# PA.net
KiCad netlist of a schematic drawn in EAGLE
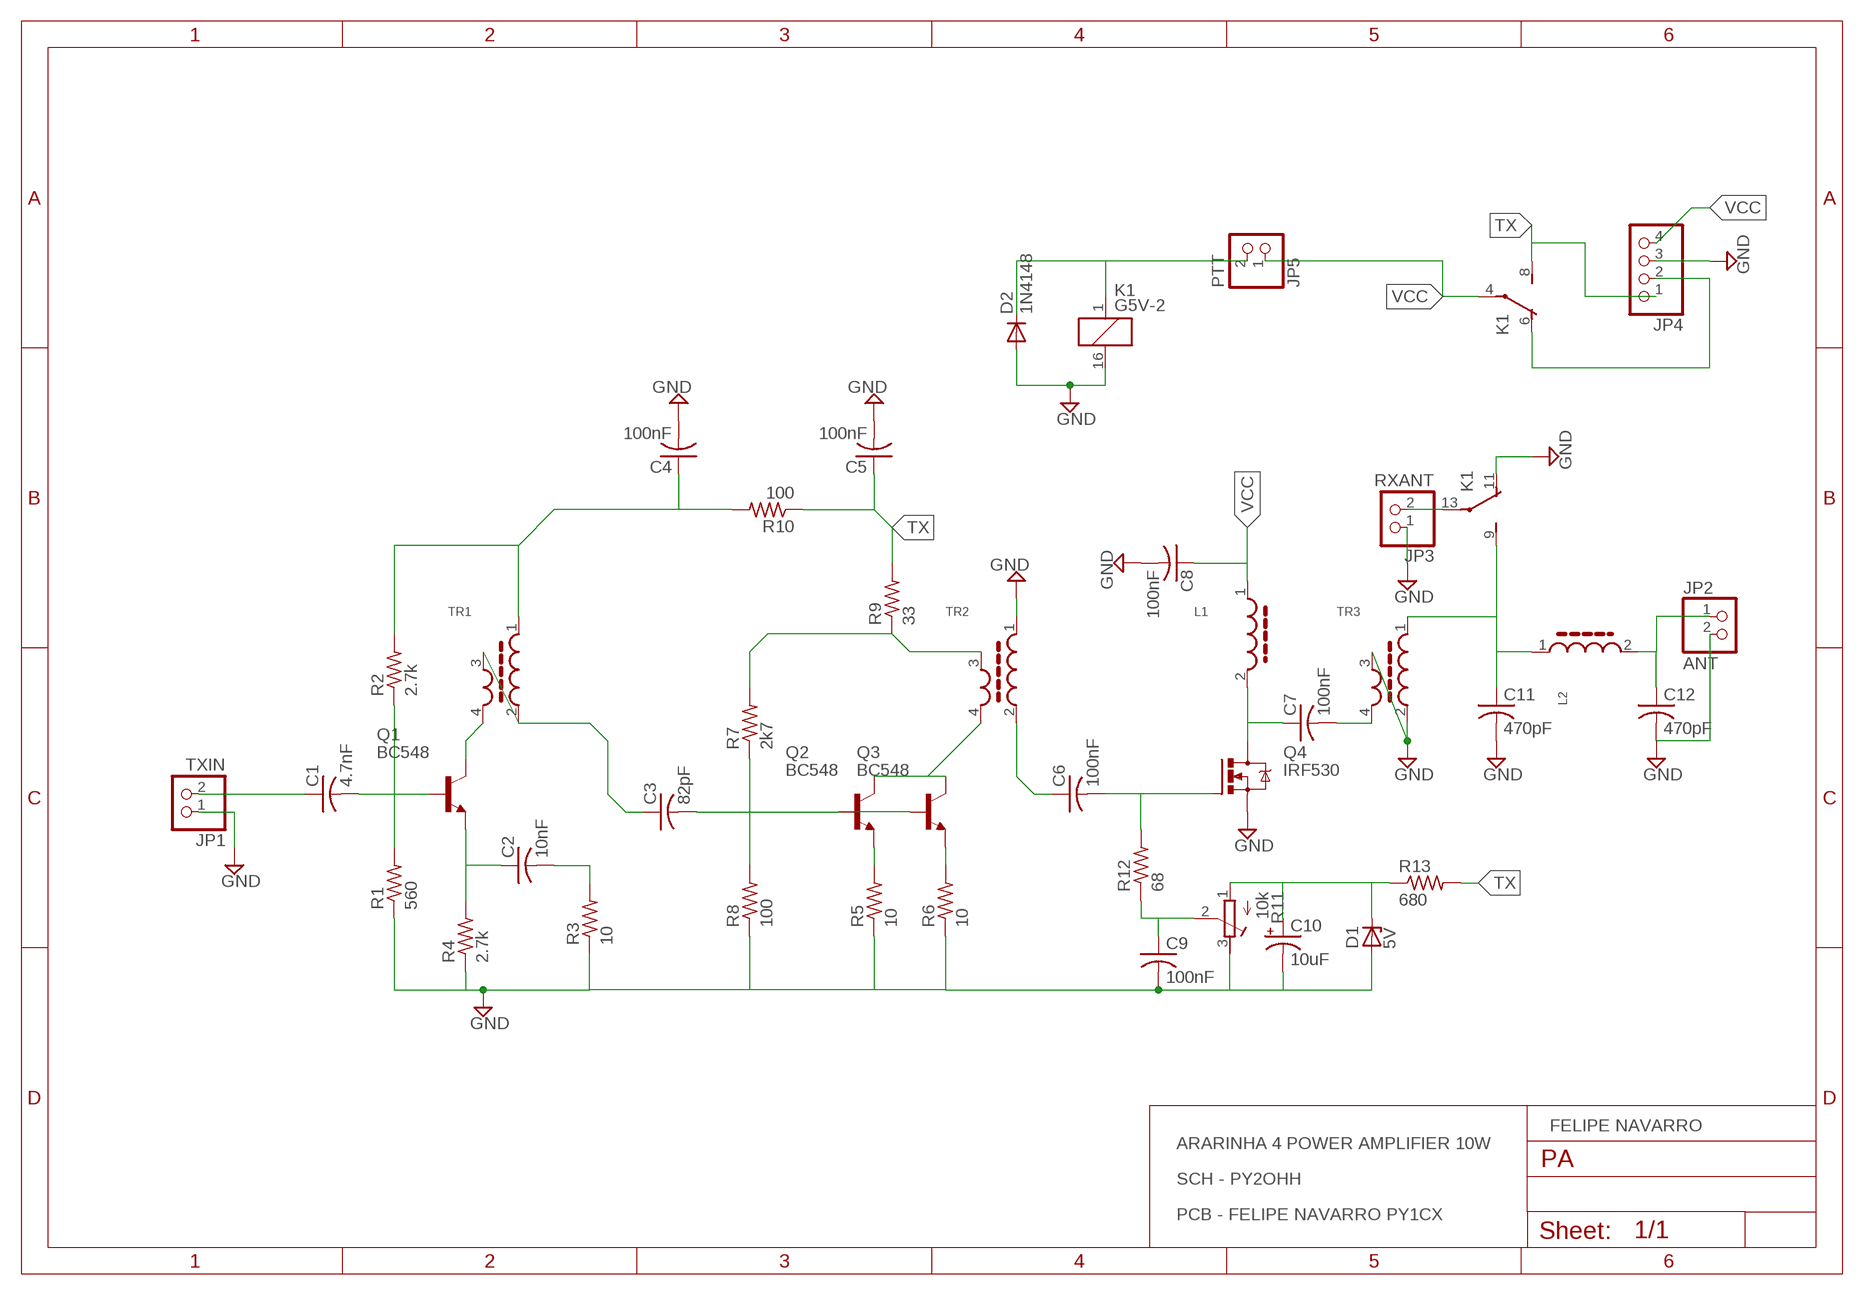
[diagram p0: schematic, sheet 1]

(export (version "E")
  (design (tool "Eeschema 10.0.6"))
  (components
    (comp (ref "C1")
      (value "4.7nF")
      (footprint "eagle-import:C050-030X075")
      (libsource (lib "eagle-import") (part "C-US050-030X075"))
    )
    (comp (ref "C2")
      (value "10nF")
      (footprint "eagle-import:C050-030X075")
      (libsource (lib "eagle-import") (part "C-US050-030X075"))
    )
    (comp (ref "C3")
      (value "82pF")
      (footprint "eagle-import:C050-030X075")
      (libsource (lib "eagle-import") (part "C-US050-030X075"))
    )
    (comp (ref "C4")
      (value "100nF")
      (footprint "eagle-import:C050-030X075")
      (libsource (lib "eagle-import") (part "C-US050-030X075"))
    )
    (comp (ref "C5")
      (value "100nF")
      (footprint "eagle-import:C050-030X075")
      (libsource (lib "eagle-import") (part "C-US050-030X075"))
    )
    (comp (ref "C6")
      (value "100nF")
      (footprint "eagle-import:C050-030X075")
      (libsource (lib "eagle-import") (part "C-US050-030X075"))
    )
    (comp (ref "C7")
      (value "100nF")
      (footprint "eagle-import:C050-030X075")
      (libsource (lib "eagle-import") (part "C-US050-030X075"))
    )
    (comp (ref "C8")
      (value "100nF")
      (footprint "eagle-import:C050-030X075")
      (libsource (lib "eagle-import") (part "C-US050-030X075"))
    )
    (comp (ref "C9")
      (value "100nF")
      (footprint "eagle-import:C050-030X075")
      (libsource (lib "eagle-import") (part "C-US050-030X075"))
    )
    (comp (ref "C10")
      (value "10uF")
      (footprint "eagle-import:E3,5-8")
      (libsource (lib "eagle-import") (part "CPOL-USE3.5-8"))
    )
    (comp (ref "C11")
      (value "470pF")
      (footprint "eagle-import:C050-030X075")
      (libsource (lib "eagle-import") (part "C-US050-030X075"))
    )
    (comp (ref "C12")
      (value "470pF")
      (footprint "eagle-import:C050-030X075")
      (libsource (lib "eagle-import") (part "C-US050-030X075"))
    )
    (comp (ref "D1")
      (value "5V")
      (footprint "eagle-import:DO35Z10")
      (libsource (lib "eagle-import") (part "ZTE"))
    )
    (comp (ref "D2")
      (value "1N4148")
      (footprint "eagle-import:DO35-7")
      (libsource (lib "eagle-import") (part "1N4148DO35-7"))
    )
    (comp (ref "JP1")
      (value "TXIN")
      (footprint "eagle-import:1X02")
      (libsource (lib "eagle-import") (part "PINHD-1X2"))
    )
    (comp (ref "JP2")
      (value "ANT")
      (footprint "eagle-import:1X02")
      (libsource (lib "eagle-import") (part "PINHD-1X2"))
    )
    (comp (ref "JP3")
      (value "RXANT")
      (footprint "eagle-import:1X02")
      (libsource (lib "eagle-import") (part "PINHD-1X2"))
    )
    (comp (ref "JP4")
      (value "PINHD-1X4")
      (footprint "eagle-import:1X04")
      (libsource (lib "eagle-import") (part "PINHD-1X4"))
    )
    (comp (ref "JP5")
      (value "PTT")
      (footprint "eagle-import:1X02")
      (libsource (lib "eagle-import") (part "PINHD-1X2"))
    )
    (comp (ref "K1")
      (value "G5V-2")
      (footprint "eagle-import:G5V-2")
      (fields (field (name "MPN") "G5V-2 5DC"))
      (libsource (lib "eagle-import") (part "G5V-2"))
    )
    (comp (ref "L1")
      (value "TOROID-T37-2PIN")
      (footprint "eagle-import:TOROID-T37-2PIN")
      (libsource (lib "eagle-import") (part "TOROID-T37-2PIN"))
    )
    (comp (ref "L2")
      (value "TOROID-T37-2PIN")
      (footprint "eagle-import:TOROID-T37-2PIN")
      (libsource (lib "eagle-import") (part "TOROID-T37-2PIN"))
    )
    (comp (ref "Q1")
      (value "BC548")
      (footprint "eagle-import:TO92-EBC")
      (libsource (lib "eagle-import") (part "BC548"))
    )
    (comp (ref "Q2")
      (value "BC548")
      (footprint "eagle-import:TO92-EBC")
      (libsource (lib "eagle-import") (part "BC548"))
    )
    (comp (ref "Q3")
      (value "BC548")
      (footprint "eagle-import:TO92-EBC")
      (libsource (lib "eagle-import") (part "BC548"))
    )
    (comp (ref "Q4")
      (value "IRF530")
      (footprint "eagle-import:TO220BV")
      (libsource (lib "eagle-import") (part "IRF530"))
    )
    (comp (ref "R1")
      (value "560")
      (footprint "eagle-import:0204_7")
      (libsource (lib "eagle-import") (part "R-US_0204/7"))
    )
    (comp (ref "R2")
      (value "2.7k")
      (footprint "eagle-import:0204_7")
      (libsource (lib "eagle-import") (part "R-US_0204/7"))
    )
    (comp (ref "R3")
      (value "10")
      (footprint "eagle-import:0204_7")
      (libsource (lib "eagle-import") (part "R-US_0204/7"))
    )
    (comp (ref "R4")
      (value "2.7k")
      (footprint "eagle-import:0204_7")
      (libsource (lib "eagle-import") (part "R-US_0204/7"))
    )
    (comp (ref "R5")
      (value "10")
      (footprint "eagle-import:0204_7")
      (libsource (lib "eagle-import") (part "R-US_0204/7"))
    )
    (comp (ref "R6")
      (value "10")
      (footprint "eagle-import:0204_7")
      (libsource (lib "eagle-import") (part "R-US_0204/7"))
    )
    (comp (ref "R7")
      (value "2k7")
      (footprint "eagle-import:0204_7")
      (libsource (lib "eagle-import") (part "R-US_0204/7"))
    )
    (comp (ref "R8")
      (value "100")
      (footprint "eagle-import:0204_7")
      (libsource (lib "eagle-import") (part "R-US_0204/7"))
    )
    (comp (ref "R9")
      (value "33")
      (footprint "eagle-import:0204_7")
      (libsource (lib "eagle-import") (part "R-US_0204/7"))
    )
    (comp (ref "R10")
      (value "100")
      (footprint "eagle-import:0204_7")
      (libsource (lib "eagle-import") (part "R-US_0204/7"))
    )
    (comp (ref "R11")
      (value "10k")
      (footprint "eagle-import:RTRIM64W")
      (libsource (lib "eagle-import") (part "R-TRIMM64W"))
    )
    (comp (ref "R12")
      (value "68")
      (footprint "eagle-import:0204_7")
      (libsource (lib "eagle-import") (part "R-US_0204/7"))
    )
    (comp (ref "R13")
      (value "680")
      (footprint "eagle-import:0204_7")
      (libsource (lib "eagle-import") (part "R-US_0204/7"))
    )
    (comp (ref "TR1")
      (value "TOROID-T37-4PIN")
      (footprint "eagle-import:TOROID-T37-4PIN")
      (libsource (lib "eagle-import") (part "TOROID-T37-4PIN"))
    )
    (comp (ref "TR2")
      (value "TOROID-T37-4PIN")
      (footprint "eagle-import:TOROID-T37-4PIN")
      (libsource (lib "eagle-import") (part "TOROID-T37-4PIN"))
    )
    (comp (ref "TR3")
      (value "TOROID-T37-4PIN")
      (footprint "eagle-import:TOROID-T37-4PIN")
      (libsource (lib "eagle-import") (part "TOROID-T37-4PIN"))
    )
  )
  (nets
    (net (code "1") (name "GND") (class "Default")
      (node (ref "C10") (pin "-") (pinfunction "-_-") (pintype "passive"))
      (node (ref "C11") (pin "2") (pinfunction "2_2") (pintype "passive"))
      (node (ref "C12") (pin "2") (pinfunction "2_2") (pintype "passive"))
      (node (ref "C4") (pin "2") (pinfunction "2_2") (pintype "passive"))
      (node (ref "C5") (pin "2") (pinfunction "2_2") (pintype "passive"))
      (node (ref "C8") (pin "2") (pinfunction "2_2") (pintype "passive"))
      (node (ref "C9") (pin "2") (pinfunction "2_2") (pintype "passive"))
      (node (ref "D1") (pin "A") (pinfunction "A_A") (pintype "passive"))
      (node (ref "D2") (pin "A") (pinfunction "A_A") (pintype "passive"))
      (node (ref "JP1") (pin "1") (pinfunction "1_1") (pintype "passive"))
      (node (ref "JP2") (pin "2") (pinfunction "2_2") (pintype "passive"))
      (node (ref "JP3") (pin "1") (pinfunction "1_1") (pintype "passive"))
      (node (ref "JP4") (pin "3") (pinfunction "3_3") (pintype "passive"))
      (node (ref "K1") (pin "11") (pinfunction "O_11") (pintype "passive"))
      (node (ref "K1") (pin "16") (pinfunction "2_16") (pintype "passive"))
      (node (ref "Q4") (pin "S") (pinfunction "S_S") (pintype "passive"))
      (node (ref "R1") (pin "1") (pinfunction "1_1") (pintype "passive"))
      (node (ref "R11") (pin "3") (pinfunction "A_3") (pintype "passive"))
      (node (ref "R3") (pin "1") (pinfunction "1_1") (pintype "passive"))
      (node (ref "R4") (pin "1") (pinfunction "1_1") (pintype "passive"))
      (node (ref "R5") (pin "1") (pinfunction "1_1") (pintype "passive"))
      (node (ref "R6") (pin "1") (pinfunction "1_1") (pintype "passive"))
      (node (ref "R8") (pin "1") (pinfunction "1_1") (pintype "passive"))
      (node (ref "TR2") (pin "1") (pinfunction "1_1") (pintype "bidirectional"))
      (node (ref "TR3") (pin "2") (pinfunction "2_2") (pintype "bidirectional"))
      (node (ref "TR3") (pin "3") (pinfunction "3_3") (pintype "bidirectional"))
    )
    (net (code "2") (name "Net-(C1-Pad1)") (class "Default")
      (node (ref "C1") (pin "1") (pinfunction "1_1") (pintype "passive"))
      (node (ref "JP1") (pin "2") (pinfunction "2_2") (pintype "passive"))
    )
    (net (code "3") (name "Net-(C1-Pad2)") (class "Default")
      (node (ref "C1") (pin "2") (pinfunction "2_2") (pintype "passive"))
      (node (ref "Q1") (pin "B") (pinfunction "B_B") (pintype "passive"))
      (node (ref "R1") (pin "2") (pinfunction "2_2") (pintype "passive"))
      (node (ref "R2") (pin "1") (pinfunction "1_1") (pintype "passive"))
    )
    (net (code "4") (name "Net-(C2-Pad1)") (class "Default")
      (node (ref "C2") (pin "1") (pinfunction "1_1") (pintype "passive"))
      (node (ref "Q1") (pin "E") (pinfunction "E_E") (pintype "passive"))
      (node (ref "R4") (pin "2") (pinfunction "2_2") (pintype "passive"))
    )
    (net (code "5") (name "Net-(C2-Pad2)") (class "Default")
      (node (ref "C2") (pin "2") (pinfunction "2_2") (pintype "passive"))
      (node (ref "R3") (pin "2") (pinfunction "2_2") (pintype "passive"))
    )
    (net (code "6") (name "Net-(C3-Pad1)") (class "Default")
      (node (ref "C3") (pin "1") (pinfunction "1_1") (pintype "passive"))
      (node (ref "TR1") (pin "2") (pinfunction "2_2") (pintype "bidirectional"))
      (node (ref "TR1") (pin "3") (pinfunction "3_3") (pintype "bidirectional"))
    )
    (net (code "7") (name "Net-(C3-Pad2)") (class "Default")
      (node (ref "C3") (pin "2") (pinfunction "2_2") (pintype "passive"))
      (node (ref "Q2") (pin "B") (pinfunction "B_B") (pintype "passive"))
      (node (ref "Q3") (pin "B") (pinfunction "B_B") (pintype "passive"))
      (node (ref "R7") (pin "1") (pinfunction "1_1") (pintype "passive"))
      (node (ref "R8") (pin "2") (pinfunction "2_2") (pintype "passive"))
    )
    (net (code "8") (name "Net-(C4-Pad1)") (class "Default")
      (node (ref "C4") (pin "1") (pinfunction "1_1") (pintype "passive"))
      (node (ref "R10") (pin "2") (pinfunction "2_2") (pintype "passive"))
      (node (ref "R2") (pin "2") (pinfunction "2_2") (pintype "passive"))
      (node (ref "TR1") (pin "1") (pinfunction "1_1") (pintype "bidirectional"))
    )
    (net (code "9") (name "Net-(C6-Pad1)") (class "Default")
      (node (ref "C6") (pin "1") (pinfunction "1_1") (pintype "passive"))
      (node (ref "TR2") (pin "2") (pinfunction "2_2") (pintype "bidirectional"))
    )
    (net (code "10") (name "Net-(C6-Pad2)") (class "Default")
      (node (ref "C6") (pin "2") (pinfunction "2_2") (pintype "passive"))
      (node (ref "Q4") (pin "G") (pinfunction "G_G") (pintype "passive"))
      (node (ref "R12") (pin "2") (pinfunction "2_2") (pintype "passive"))
    )
    (net (code "11") (name "Net-(C7-Pad1)") (class "Default")
      (node (ref "C7") (pin "1") (pinfunction "1_1") (pintype "passive"))
      (node (ref "L1") (pin "2") (pinfunction "2_2") (pintype "bidirectional"))
      (node (ref "Q4") (pin "D") (pinfunction "D_D") (pintype "passive"))
    )
    (net (code "12") (name "Net-(C7-Pad2)") (class "Default")
      (node (ref "C7") (pin "2") (pinfunction "2_2") (pintype "passive"))
      (node (ref "TR3") (pin "4") (pinfunction "4_4") (pintype "bidirectional"))
    )
    (net (code "13") (name "Net-(C12-Pad1)") (class "Default")
      (node (ref "C12") (pin "1") (pinfunction "1_1") (pintype "passive"))
      (node (ref "JP2") (pin "1") (pinfunction "1_1") (pintype "passive"))
      (node (ref "L2") (pin "2") (pinfunction "2_2") (pintype "bidirectional"))
    )
    (net (code "14") (name "Net-(D2-PadC)") (class "Default")
      (node (ref "D2") (pin "C") (pinfunction "C_C") (pintype "passive"))
      (node (ref "JP5") (pin "2") (pinfunction "2_2") (pintype "passive"))
      (node (ref "K1") (pin "1") (pinfunction "1_1") (pintype "passive"))
    )
    (net (code "15") (name "Net-(K1A-O)") (class "Default")
      (node (ref "JP4") (pin "2") (pinfunction "2_2") (pintype "passive"))
      (node (ref "K1") (pin "6") (pinfunction "O_6") (pintype "passive"))
    )
    (net (code "16") (name "Net-(K1B-P)") (class "Default")
      (node (ref "JP3") (pin "2") (pinfunction "2_2") (pintype "passive"))
      (node (ref "K1") (pin "13") (pinfunction "P_13") (pintype "passive"))
    )
    (net (code "17") (name "Net-(K1B-S)") (class "Default")
      (node (ref "C11") (pin "1") (pinfunction "1_1") (pintype "passive"))
      (node (ref "K1") (pin "9") (pinfunction "S_9") (pintype "passive"))
      (node (ref "L2") (pin "1") (pinfunction "1_1") (pintype "bidirectional"))
      (node (ref "TR3") (pin "1") (pinfunction "1_1") (pintype "bidirectional"))
    )
    (net (code "18") (name "Net-(Q1-PadC)") (class "Default")
      (node (ref "Q1") (pin "C") (pinfunction "C_C") (pintype "passive"))
      (node (ref "TR1") (pin "4") (pinfunction "4_4") (pintype "bidirectional"))
    )
    (net (code "19") (name "Net-(Q2-PadC)") (class "Default")
      (node (ref "Q2") (pin "C") (pinfunction "C_C") (pintype "passive"))
      (node (ref "Q3") (pin "C") (pinfunction "C_C") (pintype "passive"))
      (node (ref "TR2") (pin "4") (pinfunction "4_4") (pintype "bidirectional"))
    )
    (net (code "20") (name "Net-(Q2-PadE)") (class "Default")
      (node (ref "Q2") (pin "E") (pinfunction "E_E") (pintype "passive"))
      (node (ref "R5") (pin "2") (pinfunction "2_2") (pintype "passive"))
    )
    (net (code "21") (name "Net-(Q3-PadE)") (class "Default")
      (node (ref "Q3") (pin "E") (pinfunction "E_E") (pintype "passive"))
      (node (ref "R6") (pin "2") (pinfunction "2_2") (pintype "passive"))
    )
    (net (code "22") (name "Net-(R7-Pad2)") (class "Default")
      (node (ref "R7") (pin "2") (pinfunction "2_2") (pintype "passive"))
      (node (ref "R9") (pin "1") (pinfunction "1_1") (pintype "passive"))
      (node (ref "TR2") (pin "3") (pinfunction "3_3") (pintype "bidirectional"))
    )
    (net (code "23") (name "Net-(R11-E)") (class "Default")
      (node (ref "C10") (pin "+") (pinfunction "+_+") (pintype "passive"))
      (node (ref "D1") (pin "C") (pinfunction "C_C") (pintype "passive"))
      (node (ref "R11") (pin "1") (pinfunction "E_1") (pintype "passive"))
      (node (ref "R13") (pin "1") (pinfunction "1_1") (pintype "passive"))
    )
    (net (code "24") (name "Net-(R11-S)") (class "Default")
      (node (ref "C9") (pin "1") (pinfunction "1_1") (pintype "passive"))
      (node (ref "R11") (pin "2") (pinfunction "S_2") (pintype "passive"))
      (node (ref "R12") (pin "1") (pinfunction "1_1") (pintype "passive"))
    )
    (net (code "25") (name "TX") (class "Default")
      (node (ref "C5") (pin "1") (pinfunction "1_1") (pintype "passive"))
      (node (ref "JP4") (pin "1") (pinfunction "1_1") (pintype "passive"))
      (node (ref "K1") (pin "8") (pinfunction "S_8") (pintype "passive"))
      (node (ref "R10") (pin "1") (pinfunction "1_1") (pintype "passive"))
      (node (ref "R13") (pin "2") (pinfunction "2_2") (pintype "passive"))
      (node (ref "R9") (pin "2") (pinfunction "2_2") (pintype "passive"))
    )
    (net (code "26") (name "VCC") (class "Default")
      (node (ref "C8") (pin "1") (pinfunction "1_1") (pintype "passive"))
      (node (ref "JP4") (pin "4") (pinfunction "4_4") (pintype "passive"))
      (node (ref "JP5") (pin "1") (pinfunction "1_1") (pintype "passive"))
      (node (ref "K1") (pin "4") (pinfunction "P_4") (pintype "passive"))
      (node (ref "L1") (pin "1") (pinfunction "1_1") (pintype "bidirectional"))
    )
  )
)
